# monitor_12.net
KiCad netlist of a schematic drawn in EAGLE
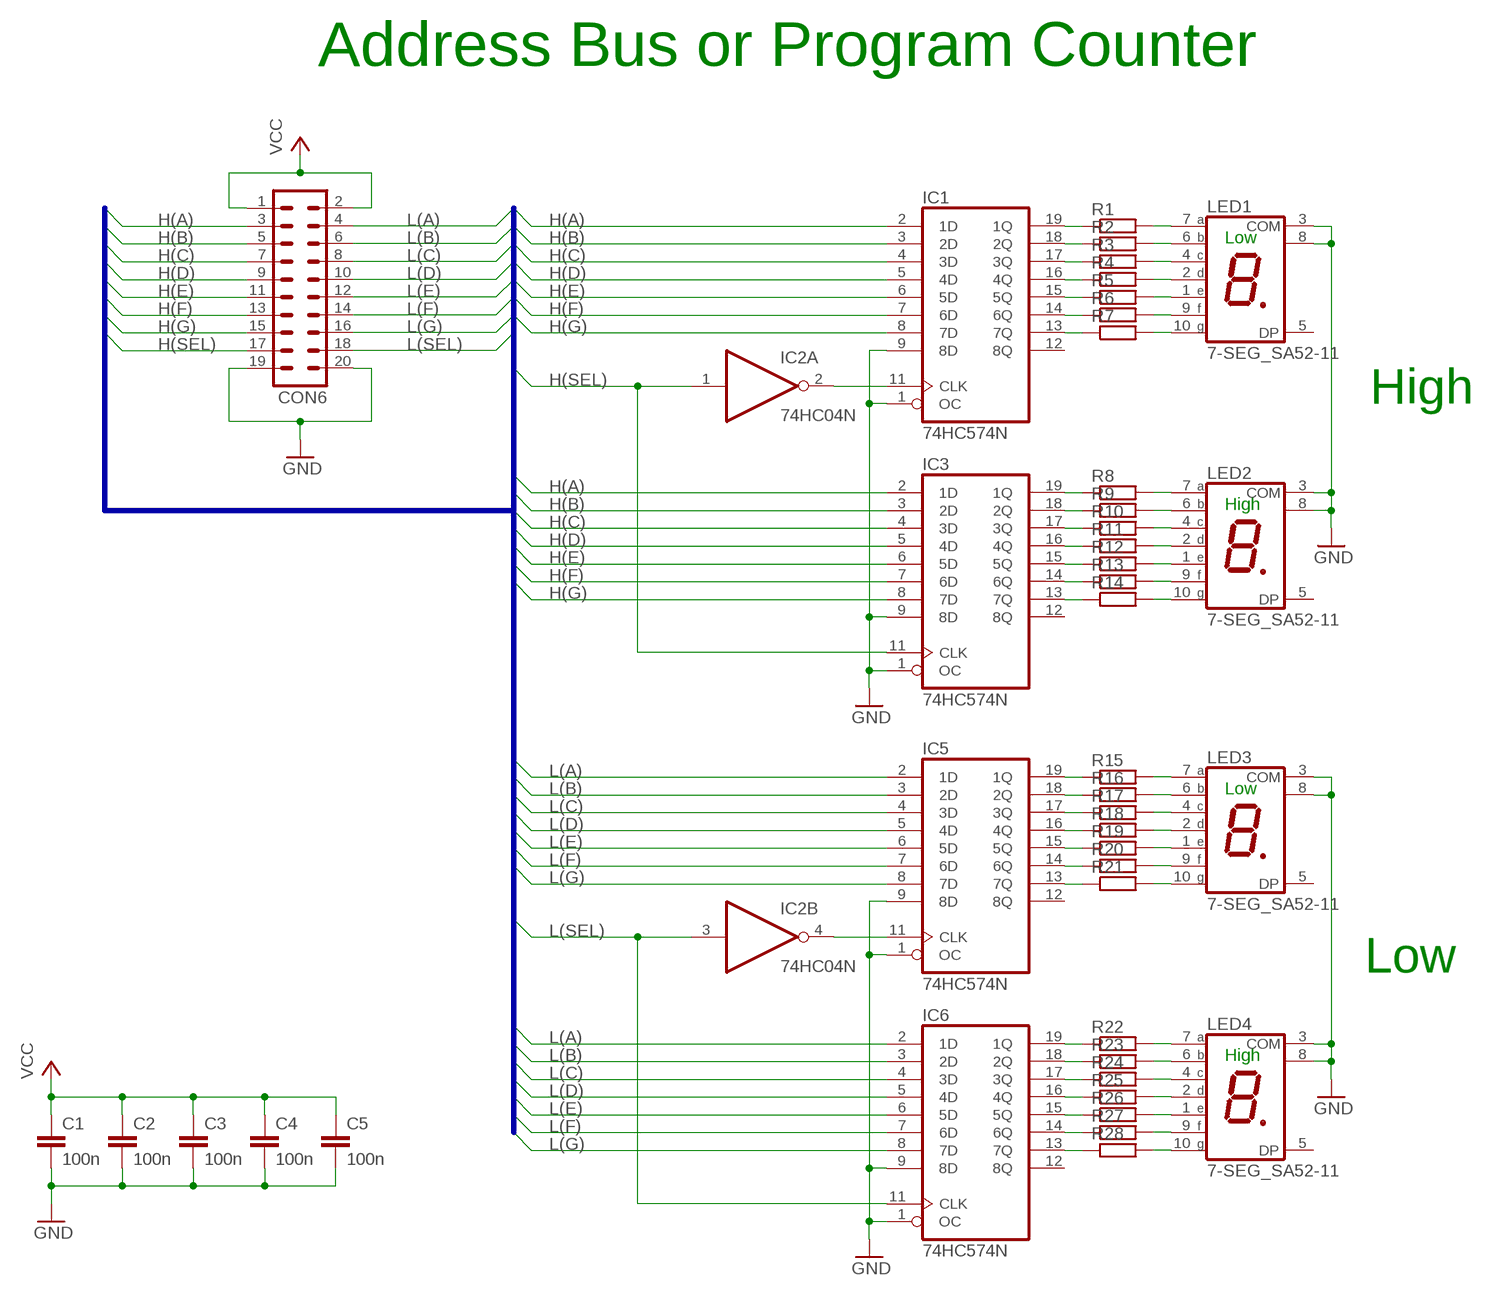
[diagram p0: schematic, sheet 1]

(export (version "E")
  (design (tool "Eeschema 10.0.6"))
  (components
    (comp (ref "C1")
      (value "100n")
      (footprint "eagle-import:C050-024X044")
      (libsource (lib "eagle-import") (part "C-EU050-024X044"))
    )
    (comp (ref "C2")
      (value "100n")
      (footprint "eagle-import:C050-024X044")
      (libsource (lib "eagle-import") (part "C-EU050-024X044"))
    )
    (comp (ref "C3")
      (value "100n")
      (footprint "eagle-import:C050-024X044")
      (libsource (lib "eagle-import") (part "C-EU050-024X044"))
    )
    (comp (ref "C4")
      (value "100n")
      (footprint "eagle-import:C050-024X044")
      (libsource (lib "eagle-import") (part "C-EU050-024X044"))
    )
    (comp (ref "C5")
      (value "100n")
      (footprint "eagle-import:C050-024X044")
      (libsource (lib "eagle-import") (part "C-EU050-024X044"))
    )
    (comp (ref "CON6")
      (value "ML20L")
      (footprint "eagle-import:ML20L")
      (libsource (lib "eagle-import") (part "ML20L"))
    )
    (comp (ref "IC1")
      (value "74HC574N")
      (footprint "eagle-import:DIL20")
      (libsource (lib "eagle-import") (part "74574NHC"))
    )
    (comp (ref "IC2")
      (value "74HC04N")
      (footprint "eagle-import:DIL14")
      (libsource (lib "eagle-import") (part "7404NHC"))
    )
    (comp (ref "IC3")
      (value "74HC574N")
      (footprint "eagle-import:DIL20")
      (libsource (lib "eagle-import") (part "74574NHC"))
    )
    (comp (ref "IC5")
      (value "74HC574N")
      (footprint "eagle-import:DIL20")
      (libsource (lib "eagle-import") (part "74574NHC"))
    )
    (comp (ref "IC6")
      (value "74HC574N")
      (footprint "eagle-import:DIL20")
      (libsource (lib "eagle-import") (part "74574NHC"))
    )
    (comp (ref "LED1")
      (value "7-SEG_SA52-11")
      (footprint "eagle-import:SA52-11")
      (libsource (lib "eagle-import") (part "7-SEG_SA52-11"))
    )
    (comp (ref "LED2")
      (value "7-SEG_SA52-11")
      (footprint "eagle-import:SA52-11")
      (libsource (lib "eagle-import") (part "7-SEG_SA52-11"))
    )
    (comp (ref "LED3")
      (value "7-SEG_SA52-11")
      (footprint "eagle-import:SA52-11")
      (libsource (lib "eagle-import") (part "7-SEG_SA52-11"))
    )
    (comp (ref "LED4")
      (value "7-SEG_SA52-11")
      (footprint "eagle-import:SA52-11")
      (libsource (lib "eagle-import") (part "7-SEG_SA52-11"))
    )
    (comp (ref "R1")
      (value "R-EU_0207/7")
      (footprint "eagle-import:0207_7")
      (libsource (lib "eagle-import") (part "R-EU_0207/7"))
    )
    (comp (ref "R2")
      (value "R-EU_0207/7")
      (footprint "eagle-import:0207_7")
      (libsource (lib "eagle-import") (part "R-EU_0207/7"))
    )
    (comp (ref "R3")
      (value "R-EU_0207/7")
      (footprint "eagle-import:0207_7")
      (libsource (lib "eagle-import") (part "R-EU_0207/7"))
    )
    (comp (ref "R4")
      (value "R-EU_0207/7")
      (footprint "eagle-import:0207_7")
      (libsource (lib "eagle-import") (part "R-EU_0207/7"))
    )
    (comp (ref "R5")
      (value "R-EU_0207/7")
      (footprint "eagle-import:0207_7")
      (libsource (lib "eagle-import") (part "R-EU_0207/7"))
    )
    (comp (ref "R6")
      (value "R-EU_0207/7")
      (footprint "eagle-import:0207_7")
      (libsource (lib "eagle-import") (part "R-EU_0207/7"))
    )
    (comp (ref "R7")
      (value "R-EU_0207/7")
      (footprint "eagle-import:0207_7")
      (libsource (lib "eagle-import") (part "R-EU_0207/7"))
    )
    (comp (ref "R8")
      (value "R-EU_0207/7")
      (footprint "eagle-import:0207_7")
      (libsource (lib "eagle-import") (part "R-EU_0207/7"))
    )
    (comp (ref "R9")
      (value "R-EU_0207/7")
      (footprint "eagle-import:0207_7")
      (libsource (lib "eagle-import") (part "R-EU_0207/7"))
    )
    (comp (ref "R10")
      (value "R-EU_0207/7")
      (footprint "eagle-import:0207_7")
      (libsource (lib "eagle-import") (part "R-EU_0207/7"))
    )
    (comp (ref "R11")
      (value "R-EU_0207/7")
      (footprint "eagle-import:0207_7")
      (libsource (lib "eagle-import") (part "R-EU_0207/7"))
    )
    (comp (ref "R12")
      (value "R-EU_0207/7")
      (footprint "eagle-import:0207_7")
      (libsource (lib "eagle-import") (part "R-EU_0207/7"))
    )
    (comp (ref "R13")
      (value "R-EU_0207/7")
      (footprint "eagle-import:0207_7")
      (libsource (lib "eagle-import") (part "R-EU_0207/7"))
    )
    (comp (ref "R14")
      (value "R-EU_0207/7")
      (footprint "eagle-import:0207_7")
      (libsource (lib "eagle-import") (part "R-EU_0207/7"))
    )
    (comp (ref "R15")
      (value "R-EU_0207/7")
      (footprint "eagle-import:0207_7")
      (libsource (lib "eagle-import") (part "R-EU_0207/7"))
    )
    (comp (ref "R16")
      (value "R-EU_0207/7")
      (footprint "eagle-import:0207_7")
      (libsource (lib "eagle-import") (part "R-EU_0207/7"))
    )
    (comp (ref "R17")
      (value "R-EU_0207/7")
      (footprint "eagle-import:0207_7")
      (libsource (lib "eagle-import") (part "R-EU_0207/7"))
    )
    (comp (ref "R18")
      (value "R-EU_0207/7")
      (footprint "eagle-import:0207_7")
      (libsource (lib "eagle-import") (part "R-EU_0207/7"))
    )
    (comp (ref "R19")
      (value "R-EU_0207/7")
      (footprint "eagle-import:0207_7")
      (libsource (lib "eagle-import") (part "R-EU_0207/7"))
    )
    (comp (ref "R20")
      (value "R-EU_0207/7")
      (footprint "eagle-import:0207_7")
      (libsource (lib "eagle-import") (part "R-EU_0207/7"))
    )
    (comp (ref "R21")
      (value "R-EU_0207/7")
      (footprint "eagle-import:0207_7")
      (libsource (lib "eagle-import") (part "R-EU_0207/7"))
    )
    (comp (ref "R22")
      (value "R-EU_0207/7")
      (footprint "eagle-import:0207_7")
      (libsource (lib "eagle-import") (part "R-EU_0207/7"))
    )
    (comp (ref "R23")
      (value "R-EU_0207/7")
      (footprint "eagle-import:0207_7")
      (libsource (lib "eagle-import") (part "R-EU_0207/7"))
    )
    (comp (ref "R24")
      (value "R-EU_0207/7")
      (footprint "eagle-import:0207_7")
      (libsource (lib "eagle-import") (part "R-EU_0207/7"))
    )
    (comp (ref "R25")
      (value "R-EU_0207/7")
      (footprint "eagle-import:0207_7")
      (libsource (lib "eagle-import") (part "R-EU_0207/7"))
    )
    (comp (ref "R26")
      (value "R-EU_0207/7")
      (footprint "eagle-import:0207_7")
      (libsource (lib "eagle-import") (part "R-EU_0207/7"))
    )
    (comp (ref "R27")
      (value "R-EU_0207/7")
      (footprint "eagle-import:0207_7")
      (libsource (lib "eagle-import") (part "R-EU_0207/7"))
    )
    (comp (ref "R28")
      (value "R-EU_0207/7")
      (footprint "eagle-import:0207_7")
      (libsource (lib "eagle-import") (part "R-EU_0207/7"))
    )
  )
  (nets
    (net (code "1") (name "/H(A)") (class "Default")
      (node (ref "CON6") (pin "3") (pinfunction "3_3") (pintype "passive"))
      (node (ref "IC1") (pin "2") (pinfunction "1D_2") (pintype "input"))
      (node (ref "IC3") (pin "2") (pinfunction "1D_2") (pintype "input"))
    )
    (net (code "2") (name "/H(B)") (class "Default")
      (node (ref "CON6") (pin "5") (pinfunction "5_5") (pintype "passive"))
      (node (ref "IC1") (pin "3") (pinfunction "2D_3") (pintype "input"))
      (node (ref "IC3") (pin "3") (pinfunction "2D_3") (pintype "input"))
    )
    (net (code "3") (name "/H(C)") (class "Default")
      (node (ref "CON6") (pin "7") (pinfunction "7_7") (pintype "passive"))
      (node (ref "IC1") (pin "4") (pinfunction "3D_4") (pintype "input"))
      (node (ref "IC3") (pin "4") (pinfunction "3D_4") (pintype "input"))
    )
    (net (code "4") (name "/H(D)") (class "Default")
      (node (ref "CON6") (pin "9") (pinfunction "9_9") (pintype "passive"))
      (node (ref "IC1") (pin "5") (pinfunction "4D_5") (pintype "input"))
      (node (ref "IC3") (pin "5") (pinfunction "4D_5") (pintype "input"))
    )
    (net (code "5") (name "/H(E)") (class "Default")
      (node (ref "CON6") (pin "11") (pinfunction "11_11") (pintype "passive"))
      (node (ref "IC1") (pin "6") (pinfunction "5D_6") (pintype "input"))
      (node (ref "IC3") (pin "6") (pinfunction "5D_6") (pintype "input"))
    )
    (net (code "6") (name "/H(F)") (class "Default")
      (node (ref "CON6") (pin "13") (pinfunction "13_13") (pintype "passive"))
      (node (ref "IC1") (pin "7") (pinfunction "6D_7") (pintype "input"))
      (node (ref "IC3") (pin "7") (pinfunction "6D_7") (pintype "input"))
    )
    (net (code "7") (name "/H(G)") (class "Default")
      (node (ref "CON6") (pin "15") (pinfunction "15_15") (pintype "passive"))
      (node (ref "IC1") (pin "8") (pinfunction "7D_8") (pintype "input"))
      (node (ref "IC3") (pin "8") (pinfunction "7D_8") (pintype "input"))
    )
    (net (code "8") (name "/H(SEL)") (class "Default")
      (node (ref "CON6") (pin "17") (pinfunction "17_17") (pintype "passive"))
      (node (ref "IC2") (pin "1") (pinfunction "I_1") (pintype "input"))
      (node (ref "IC3") (pin "11") (pinfunction "CLK_11") (pintype "input"))
    )
    (net (code "9") (name "/L(A)") (class "Default")
      (node (ref "CON6") (pin "4") (pinfunction "4_4") (pintype "passive"))
      (node (ref "IC5") (pin "2") (pinfunction "1D_2") (pintype "input"))
      (node (ref "IC6") (pin "2") (pinfunction "1D_2") (pintype "input"))
    )
    (net (code "10") (name "/L(B)") (class "Default")
      (node (ref "CON6") (pin "6") (pinfunction "6_6") (pintype "passive"))
      (node (ref "IC5") (pin "3") (pinfunction "2D_3") (pintype "input"))
      (node (ref "IC6") (pin "3") (pinfunction "2D_3") (pintype "input"))
    )
    (net (code "11") (name "/L(C)") (class "Default")
      (node (ref "CON6") (pin "8") (pinfunction "8_8") (pintype "passive"))
      (node (ref "IC5") (pin "4") (pinfunction "3D_4") (pintype "input"))
      (node (ref "IC6") (pin "4") (pinfunction "3D_4") (pintype "input"))
    )
    (net (code "12") (name "/L(D)") (class "Default")
      (node (ref "CON6") (pin "10") (pinfunction "10_10") (pintype "passive"))
      (node (ref "IC5") (pin "5") (pinfunction "4D_5") (pintype "input"))
      (node (ref "IC6") (pin "5") (pinfunction "4D_5") (pintype "input"))
    )
    (net (code "13") (name "/L(E)") (class "Default")
      (node (ref "CON6") (pin "12") (pinfunction "12_12") (pintype "passive"))
      (node (ref "IC5") (pin "6") (pinfunction "5D_6") (pintype "input"))
      (node (ref "IC6") (pin "6") (pinfunction "5D_6") (pintype "input"))
    )
    (net (code "14") (name "/L(F)") (class "Default")
      (node (ref "CON6") (pin "14") (pinfunction "14_14") (pintype "passive"))
      (node (ref "IC5") (pin "7") (pinfunction "6D_7") (pintype "input"))
      (node (ref "IC6") (pin "7") (pinfunction "6D_7") (pintype "input"))
    )
    (net (code "15") (name "/L(G)") (class "Default")
      (node (ref "CON6") (pin "16") (pinfunction "16_16") (pintype "passive"))
      (node (ref "IC5") (pin "8") (pinfunction "7D_8") (pintype "input"))
      (node (ref "IC6") (pin "8") (pinfunction "7D_8") (pintype "input"))
    )
    (net (code "16") (name "/L(SEL)") (class "Default")
      (node (ref "CON6") (pin "18") (pinfunction "18_18") (pintype "passive"))
      (node (ref "IC2") (pin "3") (pinfunction "I_3") (pintype "input"))
      (node (ref "IC6") (pin "11") (pinfunction "CLK_11") (pintype "input"))
    )
    (net (code "17") (name "GND") (class "Default")
      (node (ref "C1") (pin "2") (pinfunction "2_2") (pintype "passive"))
      (node (ref "C2") (pin "2") (pinfunction "2_2") (pintype "passive"))
      (node (ref "C3") (pin "2") (pinfunction "2_2") (pintype "passive"))
      (node (ref "C4") (pin "2") (pinfunction "2_2") (pintype "passive"))
      (node (ref "C5") (pin "2") (pinfunction "2_2") (pintype "passive"))
      (node (ref "CON6") (pin "19") (pinfunction "19_19") (pintype "passive"))
      (node (ref "CON6") (pin "20") (pinfunction "20_20") (pintype "passive"))
      (node (ref "IC1") (pin "1") (pinfunction "OC_1") (pintype "input"))
      (node (ref "IC1") (pin "9") (pinfunction "8D_9") (pintype "input"))
      (node (ref "IC3") (pin "1") (pinfunction "OC_1") (pintype "input"))
      (node (ref "IC3") (pin "9") (pinfunction "8D_9") (pintype "input"))
      (node (ref "IC5") (pin "1") (pinfunction "OC_1") (pintype "input"))
      (node (ref "IC5") (pin "9") (pinfunction "8D_9") (pintype "input"))
      (node (ref "IC6") (pin "1") (pinfunction "OC_1") (pintype "input"))
      (node (ref "IC6") (pin "9") (pinfunction "8D_9") (pintype "input"))
      (node (ref "LED1") (pin "3") (pinfunction "COM_3") (pintype "passive"))
      (node (ref "LED1") (pin "8") (pinfunction "COM_8") (pintype "passive"))
      (node (ref "LED2") (pin "3") (pinfunction "COM_3") (pintype "passive"))
      (node (ref "LED2") (pin "8") (pinfunction "COM_8") (pintype "passive"))
      (node (ref "LED3") (pin "3") (pinfunction "COM_3") (pintype "passive"))
      (node (ref "LED3") (pin "8") (pinfunction "COM_8") (pintype "passive"))
      (node (ref "LED4") (pin "3") (pinfunction "COM_3") (pintype "passive"))
      (node (ref "LED4") (pin "8") (pinfunction "COM_8") (pintype "passive"))
    )
    (net (code "18") (name "Net-(IC1A-1Q)") (class "Default")
      (node (ref "IC1") (pin "19") (pinfunction "1Q_19") (pintype "tri_state"))
      (node (ref "R1") (pin "1") (pinfunction "1_1") (pintype "passive"))
    )
    (net (code "19") (name "Net-(IC1A-2Q)") (class "Default")
      (node (ref "IC1") (pin "18") (pinfunction "2Q_18") (pintype "tri_state"))
      (node (ref "R2") (pin "1") (pinfunction "1_1") (pintype "passive"))
    )
    (net (code "20") (name "Net-(IC1A-3Q)") (class "Default")
      (node (ref "IC1") (pin "17") (pinfunction "3Q_17") (pintype "tri_state"))
      (node (ref "R3") (pin "1") (pinfunction "1_1") (pintype "passive"))
    )
    (net (code "21") (name "Net-(IC1A-4Q)") (class "Default")
      (node (ref "IC1") (pin "16") (pinfunction "4Q_16") (pintype "tri_state"))
      (node (ref "R4") (pin "1") (pinfunction "1_1") (pintype "passive"))
    )
    (net (code "22") (name "Net-(IC1A-5Q)") (class "Default")
      (node (ref "IC1") (pin "15") (pinfunction "5Q_15") (pintype "tri_state"))
      (node (ref "R5") (pin "1") (pinfunction "1_1") (pintype "passive"))
    )
    (net (code "23") (name "Net-(IC1A-6Q)") (class "Default")
      (node (ref "IC1") (pin "14") (pinfunction "6Q_14") (pintype "tri_state"))
      (node (ref "R6") (pin "1") (pinfunction "1_1") (pintype "passive"))
    )
    (net (code "24") (name "Net-(IC1A-7Q)") (class "Default")
      (node (ref "IC1") (pin "13") (pinfunction "7Q_13") (pintype "tri_state"))
      (node (ref "R7") (pin "1") (pinfunction "1_1") (pintype "passive"))
    )
    (net (code "25") (name "Net-(IC1A-CLK)") (class "Default")
      (node (ref "IC1") (pin "11") (pinfunction "CLK_11") (pintype "input"))
      (node (ref "IC2") (pin "2") (pinfunction "O_2") (pintype "output"))
    )
    (net (code "26") (name "Net-(IC2B-O)") (class "Default")
      (node (ref "IC2") (pin "4") (pinfunction "O_4") (pintype "output"))
      (node (ref "IC5") (pin "11") (pinfunction "CLK_11") (pintype "input"))
    )
    (net (code "27") (name "Net-(IC3A-1Q)") (class "Default")
      (node (ref "IC3") (pin "19") (pinfunction "1Q_19") (pintype "tri_state"))
      (node (ref "R8") (pin "1") (pinfunction "1_1") (pintype "passive"))
    )
    (net (code "28") (name "Net-(IC3A-2Q)") (class "Default")
      (node (ref "IC3") (pin "18") (pinfunction "2Q_18") (pintype "tri_state"))
      (node (ref "R9") (pin "1") (pinfunction "1_1") (pintype "passive"))
    )
    (net (code "29") (name "Net-(IC3A-3Q)") (class "Default")
      (node (ref "IC3") (pin "17") (pinfunction "3Q_17") (pintype "tri_state"))
      (node (ref "R10") (pin "1") (pinfunction "1_1") (pintype "passive"))
    )
    (net (code "30") (name "Net-(IC3A-4Q)") (class "Default")
      (node (ref "IC3") (pin "16") (pinfunction "4Q_16") (pintype "tri_state"))
      (node (ref "R11") (pin "1") (pinfunction "1_1") (pintype "passive"))
    )
    (net (code "31") (name "Net-(IC3A-5Q)") (class "Default")
      (node (ref "IC3") (pin "15") (pinfunction "5Q_15") (pintype "tri_state"))
      (node (ref "R12") (pin "1") (pinfunction "1_1") (pintype "passive"))
    )
    (net (code "32") (name "Net-(IC3A-6Q)") (class "Default")
      (node (ref "IC3") (pin "14") (pinfunction "6Q_14") (pintype "tri_state"))
      (node (ref "R13") (pin "1") (pinfunction "1_1") (pintype "passive"))
    )
    (net (code "33") (name "Net-(IC3A-7Q)") (class "Default")
      (node (ref "IC3") (pin "13") (pinfunction "7Q_13") (pintype "tri_state"))
      (node (ref "R14") (pin "1") (pinfunction "1_1") (pintype "passive"))
    )
    (net (code "34") (name "Net-(IC5A-1Q)") (class "Default")
      (node (ref "IC5") (pin "19") (pinfunction "1Q_19") (pintype "tri_state"))
      (node (ref "R15") (pin "1") (pinfunction "1_1") (pintype "passive"))
    )
    (net (code "35") (name "Net-(IC5A-2Q)") (class "Default")
      (node (ref "IC5") (pin "18") (pinfunction "2Q_18") (pintype "tri_state"))
      (node (ref "R16") (pin "1") (pinfunction "1_1") (pintype "passive"))
    )
    (net (code "36") (name "Net-(IC5A-3Q)") (class "Default")
      (node (ref "IC5") (pin "17") (pinfunction "3Q_17") (pintype "tri_state"))
      (node (ref "R17") (pin "1") (pinfunction "1_1") (pintype "passive"))
    )
    (net (code "37") (name "Net-(IC5A-4Q)") (class "Default")
      (node (ref "IC5") (pin "16") (pinfunction "4Q_16") (pintype "tri_state"))
      (node (ref "R18") (pin "1") (pinfunction "1_1") (pintype "passive"))
    )
    (net (code "38") (name "Net-(IC5A-5Q)") (class "Default")
      (node (ref "IC5") (pin "15") (pinfunction "5Q_15") (pintype "tri_state"))
      (node (ref "R19") (pin "1") (pinfunction "1_1") (pintype "passive"))
    )
    (net (code "39") (name "Net-(IC5A-6Q)") (class "Default")
      (node (ref "IC5") (pin "14") (pinfunction "6Q_14") (pintype "tri_state"))
      (node (ref "R20") (pin "1") (pinfunction "1_1") (pintype "passive"))
    )
    (net (code "40") (name "Net-(IC5A-7Q)") (class "Default")
      (node (ref "IC5") (pin "13") (pinfunction "7Q_13") (pintype "tri_state"))
      (node (ref "R21") (pin "1") (pinfunction "1_1") (pintype "passive"))
    )
    (net (code "41") (name "Net-(IC6A-1Q)") (class "Default")
      (node (ref "IC6") (pin "19") (pinfunction "1Q_19") (pintype "tri_state"))
      (node (ref "R22") (pin "1") (pinfunction "1_1") (pintype "passive"))
    )
    (net (code "42") (name "Net-(IC6A-2Q)") (class "Default")
      (node (ref "IC6") (pin "18") (pinfunction "2Q_18") (pintype "tri_state"))
      (node (ref "R23") (pin "1") (pinfunction "1_1") (pintype "passive"))
    )
    (net (code "43") (name "Net-(IC6A-3Q)") (class "Default")
      (node (ref "IC6") (pin "17") (pinfunction "3Q_17") (pintype "tri_state"))
      (node (ref "R24") (pin "1") (pinfunction "1_1") (pintype "passive"))
    )
    (net (code "44") (name "Net-(IC6A-4Q)") (class "Default")
      (node (ref "IC6") (pin "16") (pinfunction "4Q_16") (pintype "tri_state"))
      (node (ref "R25") (pin "1") (pinfunction "1_1") (pintype "passive"))
    )
    (net (code "45") (name "Net-(IC6A-5Q)") (class "Default")
      (node (ref "IC6") (pin "15") (pinfunction "5Q_15") (pintype "tri_state"))
      (node (ref "R26") (pin "1") (pinfunction "1_1") (pintype "passive"))
    )
    (net (code "46") (name "Net-(IC6A-6Q)") (class "Default")
      (node (ref "IC6") (pin "14") (pinfunction "6Q_14") (pintype "tri_state"))
      (node (ref "R27") (pin "1") (pinfunction "1_1") (pintype "passive"))
    )
    (net (code "47") (name "Net-(IC6A-7Q)") (class "Default")
      (node (ref "IC6") (pin "13") (pinfunction "7Q_13") (pintype "tri_state"))
      (node (ref "R28") (pin "1") (pinfunction "1_1") (pintype "passive"))
    )
    (net (code "48") (name "Net-(LED1-A)") (class "Default")
      (node (ref "LED1") (pin "7") (pinfunction "A_7") (pintype "passive"))
      (node (ref "R1") (pin "2") (pinfunction "2_2") (pintype "passive"))
    )
    (net (code "49") (name "Net-(LED1-B)") (class "Default")
      (node (ref "LED1") (pin "6") (pinfunction "B_6") (pintype "passive"))
      (node (ref "R2") (pin "2") (pinfunction "2_2") (pintype "passive"))
    )
    (net (code "50") (name "Net-(LED1-C)") (class "Default")
      (node (ref "LED1") (pin "4") (pinfunction "C_4") (pintype "passive"))
      (node (ref "R3") (pin "2") (pinfunction "2_2") (pintype "passive"))
    )
    (net (code "51") (name "Net-(LED1-D)") (class "Default")
      (node (ref "LED1") (pin "2") (pinfunction "D_2") (pintype "passive"))
      (node (ref "R4") (pin "2") (pinfunction "2_2") (pintype "passive"))
    )
    (net (code "52") (name "Net-(LED1-E)") (class "Default")
      (node (ref "LED1") (pin "1") (pinfunction "E_1") (pintype "passive"))
      (node (ref "R5") (pin "2") (pinfunction "2_2") (pintype "passive"))
    )
    (net (code "53") (name "Net-(LED1-F)") (class "Default")
      (node (ref "LED1") (pin "9") (pinfunction "F_9") (pintype "passive"))
      (node (ref "R6") (pin "2") (pinfunction "2_2") (pintype "passive"))
    )
    (net (code "54") (name "Net-(LED1-G)") (class "Default")
      (node (ref "LED1") (pin "10") (pinfunction "G_10") (pintype "passive"))
      (node (ref "R7") (pin "2") (pinfunction "2_2") (pintype "passive"))
    )
    (net (code "55") (name "Net-(LED2-A)") (class "Default")
      (node (ref "LED2") (pin "7") (pinfunction "A_7") (pintype "passive"))
      (node (ref "R8") (pin "2") (pinfunction "2_2") (pintype "passive"))
    )
    (net (code "56") (name "Net-(LED2-B)") (class "Default")
      (node (ref "LED2") (pin "6") (pinfunction "B_6") (pintype "passive"))
      (node (ref "R9") (pin "2") (pinfunction "2_2") (pintype "passive"))
    )
    (net (code "57") (name "Net-(LED2-C)") (class "Default")
      (node (ref "LED2") (pin "4") (pinfunction "C_4") (pintype "passive"))
      (node (ref "R10") (pin "2") (pinfunction "2_2") (pintype "passive"))
    )
    (net (code "58") (name "Net-(LED2-D)") (class "Default")
      (node (ref "LED2") (pin "2") (pinfunction "D_2") (pintype "passive"))
      (node (ref "R11") (pin "2") (pinfunction "2_2") (pintype "passive"))
    )
    (net (code "59") (name "Net-(LED2-E)") (class "Default")
      (node (ref "LED2") (pin "1") (pinfunction "E_1") (pintype "passive"))
      (node (ref "R12") (pin "2") (pinfunction "2_2") (pintype "passive"))
    )
    (net (code "60") (name "Net-(LED2-F)") (class "Default")
      (node (ref "LED2") (pin "9") (pinfunction "F_9") (pintype "passive"))
      (node (ref "R13") (pin "2") (pinfunction "2_2") (pintype "passive"))
    )
    (net (code "61") (name "Net-(LED2-G)") (class "Default")
      (node (ref "LED2") (pin "10") (pinfunction "G_10") (pintype "passive"))
      (node (ref "R14") (pin "2") (pinfunction "2_2") (pintype "passive"))
    )
    (net (code "62") (name "Net-(LED3-A)") (class "Default")
      (node (ref "LED3") (pin "7") (pinfunction "A_7") (pintype "passive"))
      (node (ref "R15") (pin "2") (pinfunction "2_2") (pintype "passive"))
    )
    (net (code "63") (name "Net-(LED3-B)") (class "Default")
      (node (ref "LED3") (pin "6") (pinfunction "B_6") (pintype "passive"))
      (node (ref "R16") (pin "2") (pinfunction "2_2") (pintype "passive"))
    )
    (net (code "64") (name "Net-(LED3-C)") (class "Default")
      (node (ref "LED3") (pin "4") (pinfunction "C_4") (pintype "passive"))
      (node (ref "R17") (pin "2") (pinfunction "2_2") (pintype "passive"))
    )
    (net (code "65") (name "Net-(LED3-D)") (class "Default")
      (node (ref "LED3") (pin "2") (pinfunction "D_2") (pintype "passive"))
      (node (ref "R18") (pin "2") (pinfunction "2_2") (pintype "passive"))
    )
    (net (code "66") (name "Net-(LED3-E)") (class "Default")
      (node (ref "LED3") (pin "1") (pinfunction "E_1") (pintype "passive"))
      (node (ref "R19") (pin "2") (pinfunction "2_2") (pintype "passive"))
    )
    (net (code "67") (name "Net-(LED3-F)") (class "Default")
      (node (ref "LED3") (pin "9") (pinfunction "F_9") (pintype "passive"))
      (node (ref "R20") (pin "2") (pinfunction "2_2") (pintype "passive"))
    )
    (net (code "68") (name "Net-(LED3-G)") (class "Default")
      (node (ref "LED3") (pin "10") (pinfunction "G_10") (pintype "passive"))
      (node (ref "R21") (pin "2") (pinfunction "2_2") (pintype "passive"))
    )
    (net (code "69") (name "Net-(LED4-A)") (class "Default")
      (node (ref "LED4") (pin "7") (pinfunction "A_7") (pintype "passive"))
      (node (ref "R22") (pin "2") (pinfunction "2_2") (pintype "passive"))
    )
    (net (code "70") (name "Net-(LED4-B)") (class "Default")
      (node (ref "LED4") (pin "6") (pinfunction "B_6") (pintype "passive"))
      (node (ref "R23") (pin "2") (pinfunction "2_2") (pintype "passive"))
    )
    (net (code "71") (name "Net-(LED4-C)") (class "Default")
      (node (ref "LED4") (pin "4") (pinfunction "C_4") (pintype "passive"))
      (node (ref "R24") (pin "2") (pinfunction "2_2") (pintype "passive"))
    )
    (net (code "72") (name "Net-(LED4-D)") (class "Default")
      (node (ref "LED4") (pin "2") (pinfunction "D_2") (pintype "passive"))
      (node (ref "R25") (pin "2") (pinfunction "2_2") (pintype "passive"))
    )
    (net (code "73") (name "Net-(LED4-E)") (class "Default")
      (node (ref "LED4") (pin "1") (pinfunction "E_1") (pintype "passive"))
      (node (ref "R26") (pin "2") (pinfunction "2_2") (pintype "passive"))
    )
    (net (code "74") (name "Net-(LED4-F)") (class "Default")
      (node (ref "LED4") (pin "9") (pinfunction "F_9") (pintype "passive"))
      (node (ref "R27") (pin "2") (pinfunction "2_2") (pintype "passive"))
    )
    (net (code "75") (name "Net-(LED4-G)") (class "Default")
      (node (ref "LED4") (pin "10") (pinfunction "G_10") (pintype "passive"))
      (node (ref "R28") (pin "2") (pinfunction "2_2") (pintype "passive"))
    )
    (net (code "76") (name "VCC") (class "Default")
      (node (ref "C1") (pin "1") (pinfunction "1_1") (pintype "passive"))
      (node (ref "C2") (pin "1") (pinfunction "1_1") (pintype "passive"))
      (node (ref "C3") (pin "1") (pinfunction "1_1") (pintype "passive"))
      (node (ref "C4") (pin "1") (pinfunction "1_1") (pintype "passive"))
      (node (ref "C5") (pin "1") (pinfunction "1_1") (pintype "passive"))
      (node (ref "CON6") (pin "1") (pinfunction "1_1") (pintype "passive"))
      (node (ref "CON6") (pin "2") (pinfunction "2_2") (pintype "passive"))
    )
    (net (code "77") (name "unconnected-(IC1A-8Q-Pad12)") (class "Default")
      (node (ref "IC1") (pin "12") (pinfunction "8Q_12") (pintype "tri_state"))
    )
    (net (code "78") (name "unconnected-(IC3A-8Q-Pad12)") (class "Default")
      (node (ref "IC3") (pin "12") (pinfunction "8Q_12") (pintype "tri_state"))
    )
    (net (code "79") (name "unconnected-(IC5A-8Q-Pad12)") (class "Default")
      (node (ref "IC5") (pin "12") (pinfunction "8Q_12") (pintype "tri_state"))
    )
    (net (code "80") (name "unconnected-(IC6A-8Q-Pad12)") (class "Default")
      (node (ref "IC6") (pin "12") (pinfunction "8Q_12") (pintype "tri_state"))
    )
    (net (code "81") (name "unconnected-(LED1-DP-Pad5)") (class "Default")
      (node (ref "LED1") (pin "5") (pinfunction "DP_5") (pintype "passive"))
    )
    (net (code "82") (name "unconnected-(LED2-DP-Pad5)") (class "Default")
      (node (ref "LED2") (pin "5") (pinfunction "DP_5") (pintype "passive"))
    )
    (net (code "83") (name "unconnected-(LED3-DP-Pad5)") (class "Default")
      (node (ref "LED3") (pin "5") (pinfunction "DP_5") (pintype "passive"))
    )
    (net (code "84") (name "unconnected-(LED4-DP-Pad5)") (class "Default")
      (node (ref "LED4") (pin "5") (pinfunction "DP_5") (pintype "passive"))
    )
  )
)
